# Sheet1.net
KiCad netlist of a schematic drawn in Altium Designer
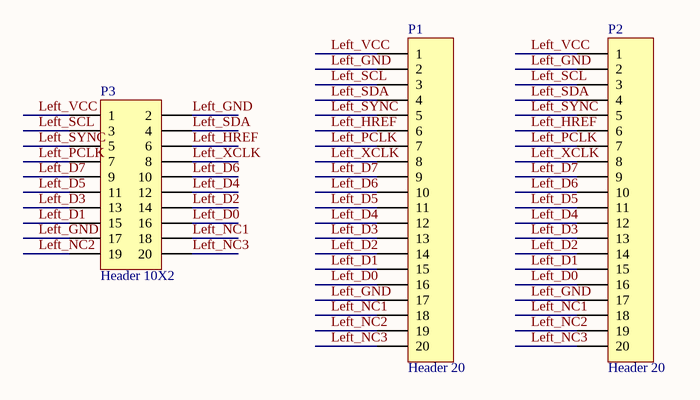
[diagram p0: Sheet1.SchDoc]

(export (version "E")
  (design (tool "Eeschema 10.0.6"))
  (components
    (comp (ref "P1")
      (value "Header 20")
      (footprint "FPC20Pin")
      (description "Header, 20-Pin")
      (fields (field (name "PUBLISHER") "Altium Limited"))
      (libsource (lib "Miscellaneous Connectors") (part "Header 20"))
    )
    (comp (ref "P2")
      (value "Header 20")
      (footprint "FPC20Pin")
      (description "Header, 20-Pin")
      (fields (field (name "PUBLISHER") "Altium Limited"))
      (libsource (lib "Miscellaneous Connectors") (part "Header 20"))
    )
    (comp (ref "P3")
      (value "Header 10X2")
      (footprint "HDR2X10")
      (description "Header, 10-Pin, Dual row")
      (fields (field (name "PUBLISHER") "Altium Limited"))
      (libsource (lib "Miscellaneous Connectors") (part "Header 10X2"))
    )
  )
  (nets
    (net (code "1") (name "/Left_D0") (class "Default")
      (node (ref "P1") (pin "16") (pinfunction "16_16") (pintype "passive"))
      (node (ref "P2") (pin "16") (pinfunction "16_16") (pintype "passive"))
      (node (ref "P3") (pin "16") (pinfunction "16_16") (pintype "passive"))
    )
    (net (code "2") (name "/Left_D1") (class "Default")
      (node (ref "P1") (pin "15") (pinfunction "15_15") (pintype "passive"))
      (node (ref "P2") (pin "15") (pinfunction "15_15") (pintype "passive"))
      (node (ref "P3") (pin "15") (pinfunction "15_15") (pintype "passive"))
    )
    (net (code "3") (name "/Left_D2") (class "Default")
      (node (ref "P1") (pin "14") (pinfunction "14_14") (pintype "passive"))
      (node (ref "P2") (pin "14") (pinfunction "14_14") (pintype "passive"))
      (node (ref "P3") (pin "14") (pinfunction "14_14") (pintype "passive"))
    )
    (net (code "4") (name "/Left_D3") (class "Default")
      (node (ref "P1") (pin "13") (pinfunction "13_13") (pintype "passive"))
      (node (ref "P2") (pin "13") (pinfunction "13_13") (pintype "passive"))
      (node (ref "P3") (pin "13") (pinfunction "13_13") (pintype "passive"))
    )
    (net (code "5") (name "/Left_D4") (class "Default")
      (node (ref "P1") (pin "12") (pinfunction "12_12") (pintype "passive"))
      (node (ref "P2") (pin "12") (pinfunction "12_12") (pintype "passive"))
      (node (ref "P3") (pin "12") (pinfunction "12_12") (pintype "passive"))
    )
    (net (code "6") (name "/Left_D5") (class "Default")
      (node (ref "P1") (pin "11") (pinfunction "11_11") (pintype "passive"))
      (node (ref "P2") (pin "11") (pinfunction "11_11") (pintype "passive"))
      (node (ref "P3") (pin "11") (pinfunction "11_11") (pintype "passive"))
    )
    (net (code "7") (name "/Left_D6") (class "Default")
      (node (ref "P1") (pin "10") (pinfunction "10_10") (pintype "passive"))
      (node (ref "P2") (pin "10") (pinfunction "10_10") (pintype "passive"))
      (node (ref "P3") (pin "10") (pinfunction "10_10") (pintype "passive"))
    )
    (net (code "8") (name "/Left_D7") (class "Default")
      (node (ref "P1") (pin "9") (pinfunction "9_9") (pintype "passive"))
      (node (ref "P2") (pin "9") (pinfunction "9_9") (pintype "passive"))
      (node (ref "P3") (pin "9") (pinfunction "9_9") (pintype "passive"))
    )
    (net (code "9") (name "/Left_GND") (class "Default")
      (node (ref "P1") (pin "17") (pinfunction "17_17") (pintype "passive"))
      (node (ref "P1") (pin "2") (pinfunction "2_2") (pintype "passive"))
      (node (ref "P2") (pin "17") (pinfunction "17_17") (pintype "passive"))
      (node (ref "P2") (pin "2") (pinfunction "2_2") (pintype "passive"))
      (node (ref "P3") (pin "17") (pinfunction "17_17") (pintype "passive"))
      (node (ref "P3") (pin "2") (pinfunction "2_2") (pintype "passive"))
    )
    (net (code "10") (name "/Left_HREF") (class "Default")
      (node (ref "P1") (pin "6") (pinfunction "6_6") (pintype "passive"))
      (node (ref "P2") (pin "6") (pinfunction "6_6") (pintype "passive"))
      (node (ref "P3") (pin "6") (pinfunction "6_6") (pintype "passive"))
    )
    (net (code "11") (name "/Left_NC1") (class "Default")
      (node (ref "P1") (pin "18") (pinfunction "18_18") (pintype "passive"))
      (node (ref "P2") (pin "18") (pinfunction "18_18") (pintype "passive"))
      (node (ref "P3") (pin "18") (pinfunction "18_18") (pintype "passive"))
    )
    (net (code "12") (name "/Left_NC2") (class "Default")
      (node (ref "P1") (pin "19") (pinfunction "19_19") (pintype "passive"))
      (node (ref "P2") (pin "19") (pinfunction "19_19") (pintype "passive"))
      (node (ref "P3") (pin "19") (pinfunction "19_19") (pintype "passive"))
    )
    (net (code "13") (name "/Left_NC3") (class "Default")
      (node (ref "P1") (pin "20") (pinfunction "20_20") (pintype "passive"))
      (node (ref "P2") (pin "20") (pinfunction "20_20") (pintype "passive"))
      (node (ref "P3") (pin "20") (pinfunction "20_20") (pintype "passive"))
    )
    (net (code "14") (name "/Left_PCLK") (class "Default")
      (node (ref "P1") (pin "7") (pinfunction "7_7") (pintype "passive"))
      (node (ref "P2") (pin "7") (pinfunction "7_7") (pintype "passive"))
      (node (ref "P3") (pin "7") (pinfunction "7_7") (pintype "passive"))
    )
    (net (code "15") (name "/Left_SCL") (class "Default")
      (node (ref "P1") (pin "3") (pinfunction "3_3") (pintype "passive"))
      (node (ref "P2") (pin "3") (pinfunction "3_3") (pintype "passive"))
      (node (ref "P3") (pin "3") (pinfunction "3_3") (pintype "passive"))
    )
    (net (code "16") (name "/Left_SDA") (class "Default")
      (node (ref "P1") (pin "4") (pinfunction "4_4") (pintype "passive"))
      (node (ref "P2") (pin "4") (pinfunction "4_4") (pintype "passive"))
      (node (ref "P3") (pin "4") (pinfunction "4_4") (pintype "passive"))
    )
    (net (code "17") (name "/Left_SYNC") (class "Default")
      (node (ref "P1") (pin "5") (pinfunction "5_5") (pintype "passive"))
      (node (ref "P2") (pin "5") (pinfunction "5_5") (pintype "passive"))
      (node (ref "P3") (pin "5") (pinfunction "5_5") (pintype "passive"))
    )
    (net (code "18") (name "/Left_VCC") (class "Default")
      (node (ref "P1") (pin "1") (pinfunction "1_1") (pintype "passive"))
      (node (ref "P2") (pin "1") (pinfunction "1_1") (pintype "passive"))
      (node (ref "P3") (pin "1") (pinfunction "1_1") (pintype "passive"))
    )
    (net (code "19") (name "/Left_XCLK") (class "Default")
      (node (ref "P1") (pin "8") (pinfunction "8_8") (pintype "passive"))
      (node (ref "P2") (pin "8") (pinfunction "8_8") (pintype "passive"))
      (node (ref "P3") (pin "8") (pinfunction "8_8") (pintype "passive"))
    )
  )
)
